# clock.net
KiCad netlist of a schematic drawn in Altium Designer
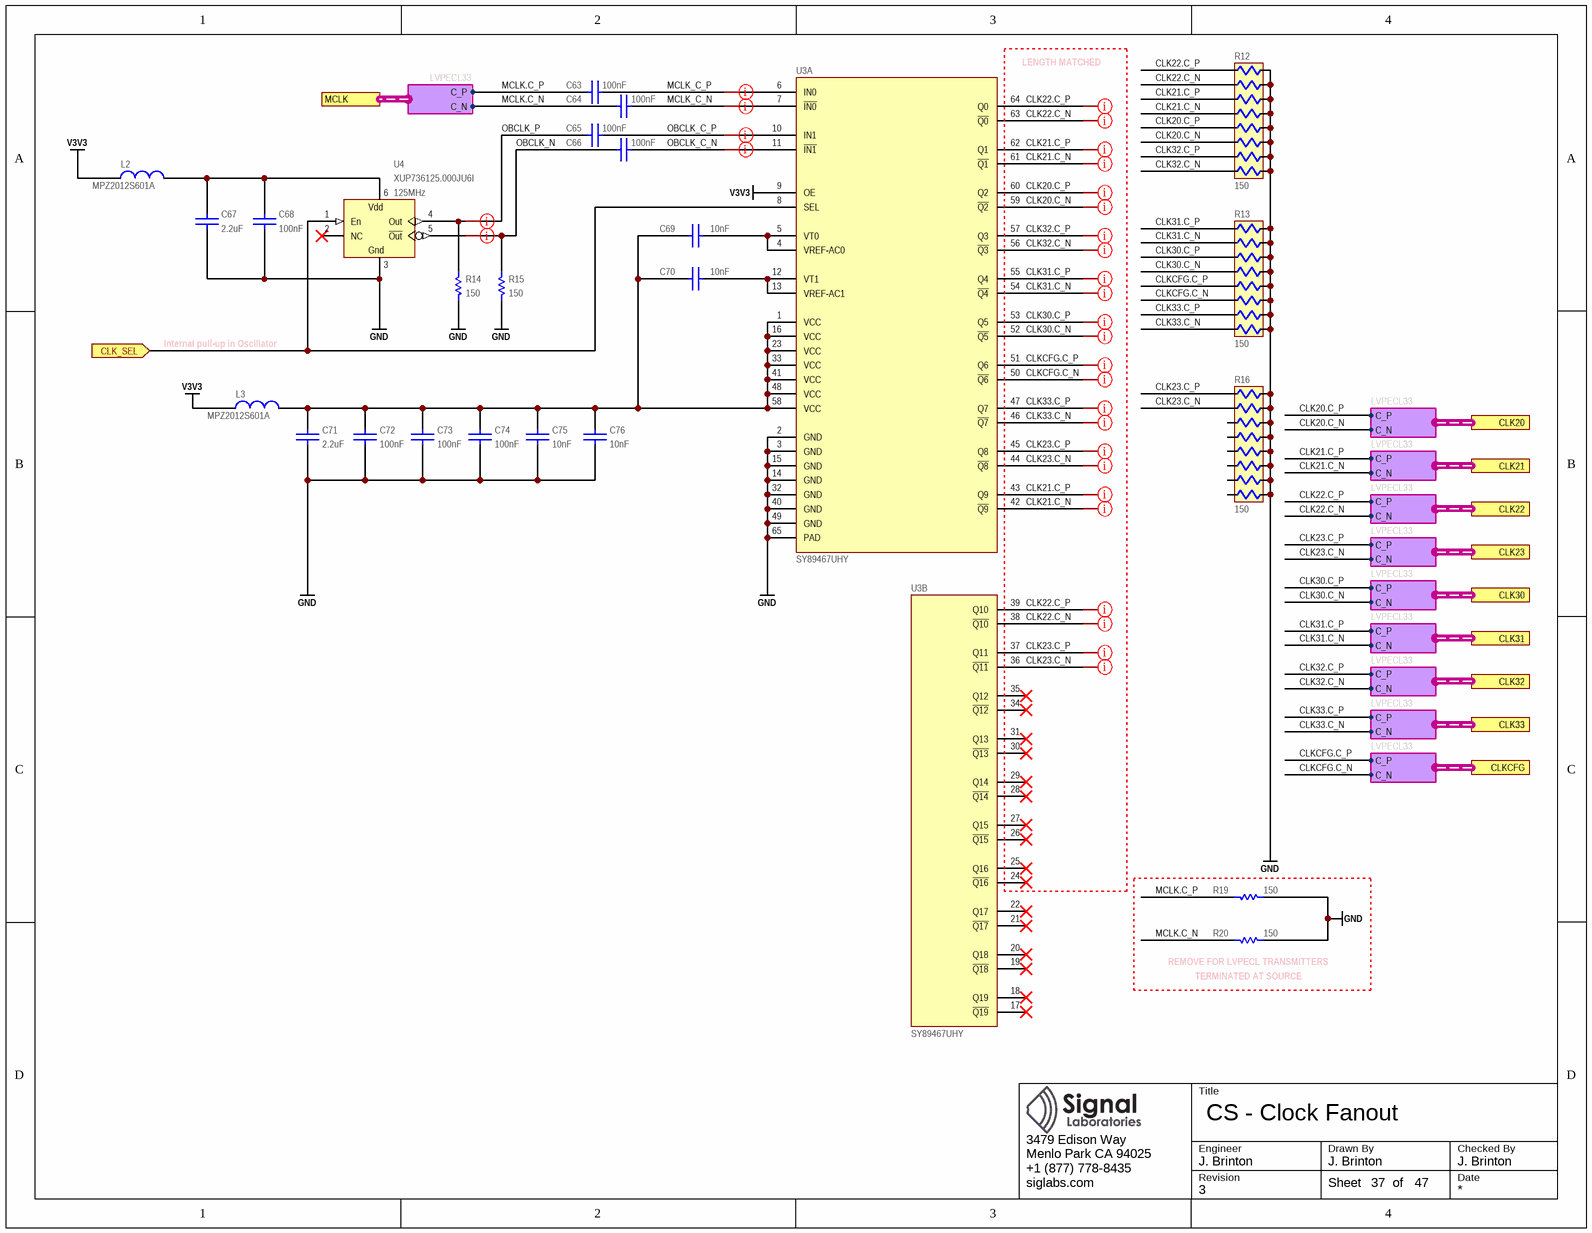
[diagram p0: clock.SchDoc]

(export (version "E")
  (design (tool "Eeschema 10.0.6"))
  (components
    (comp (ref "C63")
      (value "100nF")
      (footprint "CAPC100X50X55L25N")
      (description "Ceramic Capacitor 100nF ±10% 50V X7R 0402")
      (fields (field (name "MANUFACTURER") "Murata") (field (name "TOLERANCE") "±10%"))
      (libsource (lib "") (part "CAP_1"))
    )
    (comp (ref "C64")
      (value "100nF")
      (footprint "CAPC100X50X55L25N")
      (description "Ceramic Capacitor 100nF ±10% 50V X7R 0402")
      (fields (field (name "MANUFACTURER") "Murata") (field (name "TOLERANCE") "±10%"))
      (libsource (lib "") (part "CAP_1"))
    )
    (comp (ref "C65")
      (value "100nF")
      (footprint "CAPC100X50X55L25N")
      (description "Ceramic Capacitor 100nF ±10% 50V X7R 0402")
      (fields (field (name "MANUFACTURER") "Murata") (field (name "TOLERANCE") "±10%"))
      (libsource (lib "") (part "CAP_1"))
    )
    (comp (ref "C66")
      (value "100nF")
      (footprint "CAPC100X50X55L25N")
      (description "Ceramic Capacitor 100nF ±10% 50V X7R 0402")
      (fields (field (name "MANUFACTURER") "Murata") (field (name "TOLERANCE") "±10%"))
      (libsource (lib "") (part "CAP_1"))
    )
    (comp (ref "C67")
      (value "2.2uF")
      (footprint "CAPC160X80X90L20N")
      (description "Ceramic Capacitor 2.2uF ±20% 10V X7R 0603")
      (fields (field (name "MANUFACTURER") "TDK") (field (name "TOLERANCE") "±20%"))
      (libsource (lib "") (part "CAP_1"))
    )
    (comp (ref "C68")
      (value "100nF")
      (footprint "CAPC100X50X55L25N")
      (description "Ceramic Capacitor 100nF ±10% 50V X7R 0402")
      (fields (field (name "MANUFACTURER") "Murata") (field (name "TOLERANCE") "±10%"))
      (libsource (lib "") (part "CAP_1"))
    )
    (comp (ref "C69")
      (value "10nF")
      (footprint "CAPC100X50X55L25N")
      (description "Ceramic Capacitor 10nF ±10% 50V X7R 0402")
      (fields (field (name "MANUFACTURER") "Murata") (field (name "TOLERANCE") "±10%"))
      (libsource (lib "generic") (part "CAP"))
    )
    (comp (ref "C70")
      (value "10nF")
      (footprint "CAPC100X50X55L25N")
      (description "Ceramic Capacitor 10nF ±10% 50V X7R 0402")
      (fields (field (name "MANUFACTURER") "Murata") (field (name "TOLERANCE") "±10%"))
      (libsource (lib "generic") (part "CAP"))
    )
    (comp (ref "C71")
      (value "2.2uF")
      (footprint "CAPC160X80X90L20N")
      (description "Ceramic Capacitor 2.2uF ±20% 10V X7R 0603")
      (fields (field (name "MANUFACTURER") "TDK") (field (name "TOLERANCE") "±20%"))
      (libsource (lib "") (part "CAP_1"))
    )
    (comp (ref "C72")
      (value "100nF")
      (footprint "CAPC100X50X55L25N")
      (description "Ceramic Capacitor 100nF ±10% 50V X7R 0402")
      (fields (field (name "MANUFACTURER") "Murata") (field (name "TOLERANCE") "±10%"))
      (libsource (lib "") (part "CAP_1"))
    )
    (comp (ref "C73")
      (value "100nF")
      (footprint "CAPC100X50X55L25N")
      (description "Ceramic Capacitor 100nF ±10% 50V X7R 0402")
      (fields (field (name "MANUFACTURER") "Murata") (field (name "TOLERANCE") "±10%"))
      (libsource (lib "") (part "CAP_1"))
    )
    (comp (ref "C74")
      (value "100nF")
      (footprint "CAPC100X50X55L25N")
      (description "Ceramic Capacitor 100nF ±10% 50V X7R 0402")
      (fields (field (name "MANUFACTURER") "Murata") (field (name "TOLERANCE") "±10%"))
      (libsource (lib "") (part "CAP_1"))
    )
    (comp (ref "C75")
      (value "10nF")
      (footprint "CAPC100X50X55L25N")
      (description "Ceramic Capacitor 10nF ±10% 50V X7R 0402")
      (fields (field (name "MANUFACTURER") "Murata") (field (name "TOLERANCE") "±10%"))
      (libsource (lib "generic") (part "CAP"))
    )
    (comp (ref "C76")
      (value "10nF")
      (footprint "CAPC100X50X55L25N")
      (description "Ceramic Capacitor 10nF ±10% 50V X7R 0402")
      (fields (field (name "MANUFACTURER") "Murata") (field (name "TOLERANCE") "±10%"))
      (libsource (lib "generic") (part "CAP"))
    )
    (comp (ref "L2")
      (value "MPZ2012S601A")
      (footprint "0805")
      (description "Ferrite Bead 600-Ohm @ 100 MHz 2A 0805")
      (fields (field (name "MANUFACTURER") "TDK"))
      (libsource (lib "*") (part "INDUCTANCE1"))
    )
    (comp (ref "L3")
      (value "MPZ2012S601A")
      (footprint "0805")
      (description "Ferrite Bead 600-Ohm @ 100 MHz 2A 0805")
      (fields (field (name "MANUFACTURER") "TDK"))
      (libsource (lib "*") (part "INDUCTANCE1"))
    )
    (comp (ref "R12")
      (value "150")
      (footprint "RESCAXE16P50_380X160X55L30X35N")
      (description "8 Resistor Array 150 ±5% 0.0625W 25V 1506")
      (fields (field (name "MANUFACTURER") "Panasonic") (field (name "TOLERANCE") "±5%"))
      (libsource (lib "altium-import") (part "root_0_EXB-2HV470JV_"))
    )
    (comp (ref "R13")
      (value "150")
      (footprint "RESCAXE16P50_380X160X55L30X35N")
      (description "8 Resistor Array 150 ±5% 0.0625W 25V 1506")
      (fields (field (name "MANUFACTURER") "Panasonic") (field (name "TOLERANCE") "±5%"))
      (libsource (lib "altium-import") (part "root_0_EXB-2HV470JV_"))
    )
    (comp (ref "R14")
      (value "150")
      (footprint "RESC1005X40N")
      (description "Thick Film Resistor 150 ±1% 0.1W 50V 0402")
      (fields (field (name "TOLERANCE") "±1%") (field (name "MANUFACTURER") "Panasonic"))
      (libsource (lib "generic") (part "RES"))
    )
    (comp (ref "R15")
      (value "150")
      (footprint "RESC1005X40N")
      (description "Thick Film Resistor 150 ±1% 0.1W 50V 0402")
      (fields (field (name "TOLERANCE") "±1%") (field (name "MANUFACTURER") "Panasonic"))
      (libsource (lib "generic") (part "RES"))
    )
    (comp (ref "R16")
      (value "150")
      (footprint "RESCAXE16P50_380X160X55L30X35N")
      (description "8 Resistor Array 150 ±5% 0.0625W 25V 1506")
      (fields (field (name "MANUFACTURER") "Panasonic") (field (name "TOLERANCE") "±5%"))
      (libsource (lib "altium-import") (part "root_0_EXB-2HV470JV_"))
    )
    (comp (ref "R19")
      (value "150")
      (footprint "RESC1005X40N")
      (description "Thick Film Resistor 150 ±1% 0.1W 50V 0402")
      (fields (field (name "TOLERANCE") "±1%") (field (name "MANUFACTURER") "Panasonic"))
      (libsource (lib "generic") (part "RES"))
    )
    (comp (ref "R20")
      (value "150")
      (footprint "RESC1005X40N")
      (description "Thick Film Resistor 150 ±1% 0.1W 50V 0402")
      (fields (field (name "TOLERANCE") "±1%") (field (name "MANUFACTURER") "Panasonic"))
      (libsource (lib "generic") (part "RES"))
    )
    (comp (ref "U3")
      (value "SY89467UHY")
      (footprint "QFP65P50_1200X1200X120L60X22T500N")
      (description "2:20 LVPECL Clock Distribution Driver")
      (fields (field (name "MANUFACTURER") "Microchip"))
      (libsource (lib "microchip") (part "SY89467UHY"))
    )
    (comp (ref "U4")
      (value "125MHz")
      (footprint "fox:OSCSC6P254_735X505X140L110X140")
      (description "Oscillator 100MHz LPECL 3.3V 25ppm SMD")
      (fields
        (field (name "MANUFACTURER") "IDT")
        (field (name "MANUFACTURER P/N") "XUP736125.000JU6I")
        (field (name "Comment") "XUP736125.000JU6I")
      )
      (libsource (lib "seiko") (part "EG-2121CA 100.0000M-PHPAB"))
    )
  )
  (nets
    (net (code "2") (name "/CLK20.C_N") (class "Default")
      (node (ref "R12") (pin "6") (pinfunction "6_6") (pintype "passive"))
      (node (ref "U3") (pin "59") (pinfunction "~{Q2}_59") (pintype "passive"))
    )
    (net (code "3") (name "/CLK20.C_P") (class "Default")
      (node (ref "R12") (pin "5") (pinfunction "5_5") (pintype "passive"))
      (node (ref "U3") (pin "60") (pinfunction "Q2_60") (pintype "passive"))
    )
    (net (code "4") (name "/CLK21.C_N") (class "Default")
      (node (ref "R12") (pin "4") (pinfunction "4_4") (pintype "passive"))
      (node (ref "U3") (pin "42") (pinfunction "~{Q9}_42") (pintype "passive"))
      (node (ref "U3") (pin "61") (pinfunction "~{Q1}_61") (pintype "passive"))
    )
    (net (code "5") (name "/CLK21.C_P") (class "Default")
      (node (ref "R12") (pin "3") (pinfunction "3_3") (pintype "passive"))
      (node (ref "U3") (pin "43") (pinfunction "Q9_43") (pintype "passive"))
      (node (ref "U3") (pin "62") (pinfunction "Q1_62") (pintype "passive"))
    )
    (net (code "6") (name "/CLK22.C_N") (class "Default")
      (node (ref "R12") (pin "2") (pinfunction "2_2") (pintype "passive"))
      (node (ref "U3") (pin "38") (pinfunction "~{Q10}_38") (pintype "passive"))
      (node (ref "U3") (pin "63") (pinfunction "~{Q0}_63") (pintype "passive"))
    )
    (net (code "7") (name "/CLK22.C_P") (class "Default")
      (node (ref "R12") (pin "1") (pintype "passive"))
      (node (ref "U3") (pin "39") (pinfunction "Q10_39") (pintype "passive"))
      (node (ref "U3") (pin "64") (pinfunction "Q0_64") (pintype "passive"))
    )
    (net (code "8") (name "/CLK23.C_N") (class "Default")
      (node (ref "R16") (pin "2") (pinfunction "2_2") (pintype "passive"))
      (node (ref "U3") (pin "36") (pinfunction "~{Q11}_36") (pintype "passive"))
      (node (ref "U3") (pin "44") (pinfunction "~{Q8}_44") (pintype "passive"))
    )
    (net (code "9") (name "/CLK23.C_P") (class "Default")
      (node (ref "R16") (pin "1") (pintype "passive"))
      (node (ref "U3") (pin "37") (pinfunction "Q11_37") (pintype "passive"))
      (node (ref "U3") (pin "45") (pinfunction "Q8_45") (pintype "passive"))
    )
    (net (code "10") (name "/CLK30.C_N") (class "Default")
      (node (ref "R13") (pin "4") (pinfunction "4_4") (pintype "passive"))
      (node (ref "U3") (pin "52") (pinfunction "~{Q5}_52") (pintype "passive"))
    )
    (net (code "11") (name "/CLK30.C_P") (class "Default")
      (node (ref "R13") (pin "3") (pinfunction "3_3") (pintype "passive"))
      (node (ref "U3") (pin "53") (pinfunction "Q5_53") (pintype "passive"))
    )
    (net (code "12") (name "/CLK31.C_N") (class "Default")
      (node (ref "R13") (pin "2") (pinfunction "2_2") (pintype "passive"))
      (node (ref "U3") (pin "54") (pinfunction "~{Q4}_54") (pintype "passive"))
    )
    (net (code "13") (name "/CLK31.C_P") (class "Default")
      (node (ref "R13") (pin "1") (pintype "passive"))
      (node (ref "U3") (pin "55") (pinfunction "Q4_55") (pintype "passive"))
    )
    (net (code "14") (name "/CLK32.C_N") (class "Default")
      (node (ref "R12") (pin "8") (pinfunction "8_8") (pintype "passive"))
      (node (ref "U3") (pin "56") (pinfunction "~{Q3}_56") (pintype "passive"))
    )
    (net (code "15") (name "/CLK32.C_P") (class "Default")
      (node (ref "R12") (pin "7") (pinfunction "7_7") (pintype "passive"))
      (node (ref "U3") (pin "57") (pinfunction "Q3_57") (pintype "passive"))
    )
    (net (code "16") (name "/CLK33.C_N") (class "Default")
      (node (ref "R13") (pin "8") (pinfunction "8_8") (pintype "passive"))
      (node (ref "U3") (pin "46") (pinfunction "~{Q7}_46") (pintype "passive"))
    )
    (net (code "17") (name "/CLK33.C_P") (class "Default")
      (node (ref "R13") (pin "7") (pinfunction "7_7") (pintype "passive"))
      (node (ref "U3") (pin "47") (pinfunction "Q7_47") (pintype "passive"))
    )
    (net (code "18") (name "/CLKCFG.C_N") (class "Default")
      (node (ref "R13") (pin "6") (pinfunction "6_6") (pintype "passive"))
      (node (ref "U3") (pin "50") (pinfunction "~{Q6}_50") (pintype "passive"))
    )
    (net (code "19") (name "/CLKCFG.C_P") (class "Default")
      (node (ref "R13") (pin "5") (pinfunction "5_5") (pintype "passive"))
      (node (ref "U3") (pin "51") (pinfunction "Q6_51") (pintype "passive"))
    )
    (net (code "20") (name "/CLK_SEL") (class "Default")
      (node (ref "U3") (pin "8") (pinfunction "SEL_8") (pintype "passive"))
      (node (ref "U4") (pin "1") (pinfunction "En_1") (pintype "input"))
    )
    (net (code "21") (name "/MCLK.C_N") (class "Default")
      (node (ref "C64") (pin "2") (pinfunction "2_2") (pintype "passive"))
      (node (ref "R20") (pin "1") (pinfunction "1_1") (pintype "passive"))
    )
    (net (code "22") (name "/MCLK.C_P") (class "Default")
      (node (ref "C63") (pin "2") (pinfunction "2_2") (pintype "passive"))
      (node (ref "R19") (pin "1") (pinfunction "1_1") (pintype "passive"))
    )
    (net (code "23") (name "/MCLK_C_N") (class "Default")
      (node (ref "C64") (pin "1") (pinfunction "1_1") (pintype "passive"))
      (node (ref "U3") (pin "7") (pinfunction "~{IN0}_7") (pintype "passive"))
    )
    (net (code "24") (name "/MCLK_C_P") (class "Default")
      (node (ref "C63") (pin "1") (pinfunction "1_1") (pintype "passive"))
      (node (ref "U3") (pin "6") (pinfunction "IN0_6") (pintype "passive"))
    )
    (net (code "25") (name "/OBCLK_C_N") (class "Default")
      (node (ref "C66") (pin "1") (pinfunction "1_1") (pintype "passive"))
      (node (ref "U3") (pin "11") (pinfunction "~{IN1}_11") (pintype "passive"))
    )
    (net (code "26") (name "/OBCLK_C_P") (class "Default")
      (node (ref "C65") (pin "1") (pinfunction "1_1") (pintype "passive"))
      (node (ref "U3") (pin "10") (pinfunction "IN1_10") (pintype "passive"))
    )
    (net (code "27") (name "/OBCLK_N") (class "Default")
      (node (ref "C66") (pin "2") (pinfunction "2_2") (pintype "passive"))
      (node (ref "R15") (pin "2") (pinfunction "2_2") (pintype "passive"))
      (node (ref "U4") (pin "5") (pinfunction "~{Out}_5") (pintype "output"))
    )
    (net (code "28") (name "/OBCLK_P") (class "Default")
      (node (ref "C65") (pin "2") (pinfunction "2_2") (pintype "passive"))
      (node (ref "R14") (pin "2") (pinfunction "2_2") (pintype "passive"))
      (node (ref "U4") (pin "4") (pinfunction "Out_4") (pintype "output"))
    )
    (net (code "30") (name "GND") (class "Default")
      (node (ref "C67") (pin "1") (pinfunction "1_1") (pintype "passive"))
      (node (ref "C68") (pin "1") (pinfunction "1_1") (pintype "passive"))
      (node (ref "C71") (pin "1") (pinfunction "1_1") (pintype "passive"))
      (node (ref "C72") (pin "1") (pinfunction "1_1") (pintype "passive"))
      (node (ref "C73") (pin "1") (pinfunction "1_1") (pintype "passive"))
      (node (ref "C74") (pin "1") (pinfunction "1_1") (pintype "passive"))
      (node (ref "C75") (pin "2") (pinfunction "2_2") (pintype "passive"))
      (node (ref "C76") (pin "2") (pinfunction "2_2") (pintype "passive"))
      (node (ref "R12") (pin "10") (pinfunction "10_10") (pintype "passive"))
      (node (ref "R12") (pin "11") (pinfunction "11_11") (pintype "passive"))
      (node (ref "R12") (pin "12") (pinfunction "12_12") (pintype "passive"))
      (node (ref "R12") (pin "13") (pinfunction "13_13") (pintype "passive"))
      (node (ref "R12") (pin "14") (pinfunction "14_14") (pintype "passive"))
      (node (ref "R12") (pin "15") (pinfunction "15_15") (pintype "passive"))
      (node (ref "R12") (pin "16") (pinfunction "16_16") (pintype "passive"))
      (node (ref "R12") (pin "9") (pinfunction "9_9") (pintype "passive"))
      (node (ref "R13") (pin "10") (pinfunction "10_10") (pintype "passive"))
      (node (ref "R13") (pin "11") (pinfunction "11_11") (pintype "passive"))
      (node (ref "R13") (pin "12") (pinfunction "12_12") (pintype "passive"))
      (node (ref "R13") (pin "13") (pinfunction "13_13") (pintype "passive"))
      (node (ref "R13") (pin "14") (pinfunction "14_14") (pintype "passive"))
      (node (ref "R13") (pin "15") (pinfunction "15_15") (pintype "passive"))
      (node (ref "R13") (pin "16") (pinfunction "16_16") (pintype "passive"))
      (node (ref "R13") (pin "9") (pinfunction "9_9") (pintype "passive"))
      (node (ref "R14") (pin "1") (pinfunction "1_1") (pintype "passive"))
      (node (ref "R15") (pin "1") (pinfunction "1_1") (pintype "passive"))
      (node (ref "R16") (pin "10") (pinfunction "10_10") (pintype "passive"))
      (node (ref "R16") (pin "11") (pinfunction "11_11") (pintype "passive"))
      (node (ref "R16") (pin "12") (pinfunction "12_12") (pintype "passive"))
      (node (ref "R16") (pin "13") (pinfunction "13_13") (pintype "passive"))
      (node (ref "R16") (pin "14") (pinfunction "14_14") (pintype "passive"))
      (node (ref "R16") (pin "15") (pinfunction "15_15") (pintype "passive"))
      (node (ref "R16") (pin "16") (pinfunction "16_16") (pintype "passive"))
      (node (ref "R16") (pin "9") (pinfunction "9_9") (pintype "passive"))
      (node (ref "R19") (pin "2") (pinfunction "2_2") (pintype "passive"))
      (node (ref "R20") (pin "2") (pinfunction "2_2") (pintype "passive"))
      (node (ref "U3") (pin "14") (pinfunction "GND_14") (pintype "passive"))
      (node (ref "U3") (pin "15") (pinfunction "GND_15") (pintype "passive"))
      (node (ref "U3") (pin "2") (pinfunction "GND_2") (pintype "passive"))
      (node (ref "U3") (pin "3") (pinfunction "GND_3") (pintype "passive"))
      (node (ref "U3") (pin "32") (pinfunction "GND_32") (pintype "passive"))
      (node (ref "U3") (pin "40") (pinfunction "GND_40") (pintype "passive"))
      (node (ref "U3") (pin "49") (pinfunction "GND_49") (pintype "passive"))
      (node (ref "U3") (pin "65") (pinfunction "PAD_65") (pintype "passive"))
      (node (ref "U4") (pin "3") (pinfunction "GND_3") (pintype "power_in"))
    )
    (net (code "31") (name "Net-(C69-Pad1)") (class "Default")
      (node (ref "C69") (pin "1") (pinfunction "1_1") (pintype "passive"))
      (node (ref "C70") (pin "1") (pinfunction "1_1") (pintype "passive"))
      (node (ref "C71") (pin "2") (pinfunction "2_2") (pintype "passive"))
      (node (ref "C72") (pin "2") (pinfunction "2_2") (pintype "passive"))
      (node (ref "C73") (pin "2") (pinfunction "2_2") (pintype "passive"))
      (node (ref "C74") (pin "2") (pinfunction "2_2") (pintype "passive"))
      (node (ref "C75") (pin "1") (pinfunction "1_1") (pintype "passive"))
      (node (ref "C76") (pin "1") (pinfunction "1_1") (pintype "passive"))
      (node (ref "L3") (pin "1") (pinfunction "1_1") (pintype "passive"))
      (node (ref "U3") (pin "1") (pinfunction "VCC_1") (pintype "passive"))
      (node (ref "U3") (pin "16") (pinfunction "VCC_16") (pintype "passive"))
      (node (ref "U3") (pin "23") (pinfunction "VCC_23") (pintype "passive"))
      (node (ref "U3") (pin "33") (pinfunction "VCC_33") (pintype "passive"))
      (node (ref "U3") (pin "41") (pinfunction "VCC_41") (pintype "passive"))
      (node (ref "U3") (pin "48") (pinfunction "VCC_48") (pintype "passive"))
      (node (ref "U3") (pin "58") (pinfunction "VCC_58") (pintype "passive"))
    )
    (net (code "32") (name "Net-(U3A-VREF-AC0)") (class "Default")
      (node (ref "C69") (pin "2") (pinfunction "2_2") (pintype "passive"))
      (node (ref "U3") (pin "4") (pinfunction "VREF-AC0_4") (pintype "passive"))
      (node (ref "U3") (pin "5") (pinfunction "VT0_5") (pintype "passive"))
    )
    (net (code "33") (name "Net-(U3A-VREF-AC1)") (class "Default")
      (node (ref "C70") (pin "2") (pinfunction "2_2") (pintype "passive"))
      (node (ref "U3") (pin "12") (pinfunction "VT1_12") (pintype "passive"))
      (node (ref "U3") (pin "13") (pinfunction "VREF-AC1_13") (pintype "passive"))
    )
    (net (code "34") (name "Net-(U4-Vdd)") (class "Default")
      (node (ref "C67") (pin "2") (pinfunction "2_2") (pintype "passive"))
      (node (ref "C68") (pin "2") (pinfunction "2_2") (pintype "passive"))
      (node (ref "L2") (pin "1") (pinfunction "1_1") (pintype "passive"))
      (node (ref "U4") (pin "6") (pinfunction "Vdd_6") (pintype "power_in"))
    )
    (net (code "35") (name "V3V3") (class "Default")
      (node (ref "L2") (pin "2") (pinfunction "2_2") (pintype "passive"))
      (node (ref "L3") (pin "2") (pinfunction "2_2") (pintype "passive"))
      (node (ref "U3") (pin "9") (pinfunction "OE_9") (pintype "passive"))
    )
    (net (code "36") (name "unconnected-(R16-Pad3)") (class "Default")
      (node (ref "R16") (pin "3") (pinfunction "3_3") (pintype "passive"))
    )
    (net (code "37") (name "unconnected-(R16-Pad4)") (class "Default")
      (node (ref "R16") (pin "4") (pinfunction "4_4") (pintype "passive"))
    )
    (net (code "38") (name "unconnected-(R16-Pad5)") (class "Default")
      (node (ref "R16") (pin "5") (pinfunction "5_5") (pintype "passive"))
    )
    (net (code "39") (name "unconnected-(R16-Pad6)") (class "Default")
      (node (ref "R16") (pin "6") (pinfunction "6_6") (pintype "passive"))
    )
    (net (code "40") (name "unconnected-(R16-Pad7)") (class "Default")
      (node (ref "R16") (pin "7") (pinfunction "7_7") (pintype "passive"))
    )
    (net (code "41") (name "unconnected-(R16-Pad8)") (class "Default")
      (node (ref "R16") (pin "8") (pinfunction "8_8") (pintype "passive"))
    )
    (net (code "42") (name "unconnected-(U3B-Q12-Pad35)") (class "Default")
      (node (ref "U3") (pin "35") (pinfunction "Q12_35") (pintype "passive+no_connect"))
    )
    (net (code "43") (name "unconnected-(U3B-Q13-Pad31)") (class "Default")
      (node (ref "U3") (pin "31") (pinfunction "Q13_31") (pintype "passive+no_connect"))
    )
    (net (code "44") (name "unconnected-(U3B-Q14-Pad29)") (class "Default")
      (node (ref "U3") (pin "29") (pinfunction "Q14_29") (pintype "passive+no_connect"))
    )
    (net (code "45") (name "unconnected-(U3B-Q15-Pad27)") (class "Default")
      (node (ref "U3") (pin "27") (pinfunction "Q15_27") (pintype "passive+no_connect"))
    )
    (net (code "46") (name "unconnected-(U3B-Q16-Pad25)") (class "Default")
      (node (ref "U3") (pin "25") (pinfunction "Q16_25") (pintype "passive+no_connect"))
    )
    (net (code "47") (name "unconnected-(U3B-Q17-Pad22)") (class "Default")
      (node (ref "U3") (pin "22") (pinfunction "Q17_22") (pintype "passive+no_connect"))
    )
    (net (code "48") (name "unconnected-(U3B-Q18-Pad20)") (class "Default")
      (node (ref "U3") (pin "20") (pinfunction "Q18_20") (pintype "passive+no_connect"))
    )
    (net (code "49") (name "unconnected-(U3B-Q19-Pad18)") (class "Default")
      (node (ref "U3") (pin "18") (pinfunction "Q19_18") (pintype "passive+no_connect"))
    )
    (net (code "50") (name "unconnected-(U3B-~{Q12}-Pad34)") (class "Default")
      (node (ref "U3") (pin "34") (pinfunction "~{Q12}_34") (pintype "passive+no_connect"))
    )
    (net (code "51") (name "unconnected-(U3B-~{Q13}-Pad30)") (class "Default")
      (node (ref "U3") (pin "30") (pinfunction "~{Q13}_30") (pintype "passive+no_connect"))
    )
    (net (code "52") (name "unconnected-(U3B-~{Q14}-Pad28)") (class "Default")
      (node (ref "U3") (pin "28") (pinfunction "~{Q14}_28") (pintype "passive+no_connect"))
    )
    (net (code "53") (name "unconnected-(U3B-~{Q15}-Pad26)") (class "Default")
      (node (ref "U3") (pin "26") (pinfunction "~{Q15}_26") (pintype "passive+no_connect"))
    )
    (net (code "54") (name "unconnected-(U3B-~{Q16}-Pad24)") (class "Default")
      (node (ref "U3") (pin "24") (pinfunction "~{Q16}_24") (pintype "passive+no_connect"))
    )
    (net (code "55") (name "unconnected-(U3B-~{Q17}-Pad21)") (class "Default")
      (node (ref "U3") (pin "21") (pinfunction "~{Q17}_21") (pintype "passive+no_connect"))
    )
    (net (code "56") (name "unconnected-(U3B-~{Q18}-Pad19)") (class "Default")
      (node (ref "U3") (pin "19") (pinfunction "~{Q18}_19") (pintype "passive+no_connect"))
    )
    (net (code "57") (name "unconnected-(U3B-~{Q19}-Pad17)") (class "Default")
      (node (ref "U3") (pin "17") (pinfunction "~{Q19}_17") (pintype "passive+no_connect"))
    )
    (net (code "58") (name "unconnected-(U4-NC-Pad2)") (class "Default")
      (node (ref "U4") (pin "2") (pinfunction "NC_2") (pintype "passive+no_connect"))
    )
  )
)
